# Mainboard-v18.net
KiCad netlist of a schematic drawn in EAGLE
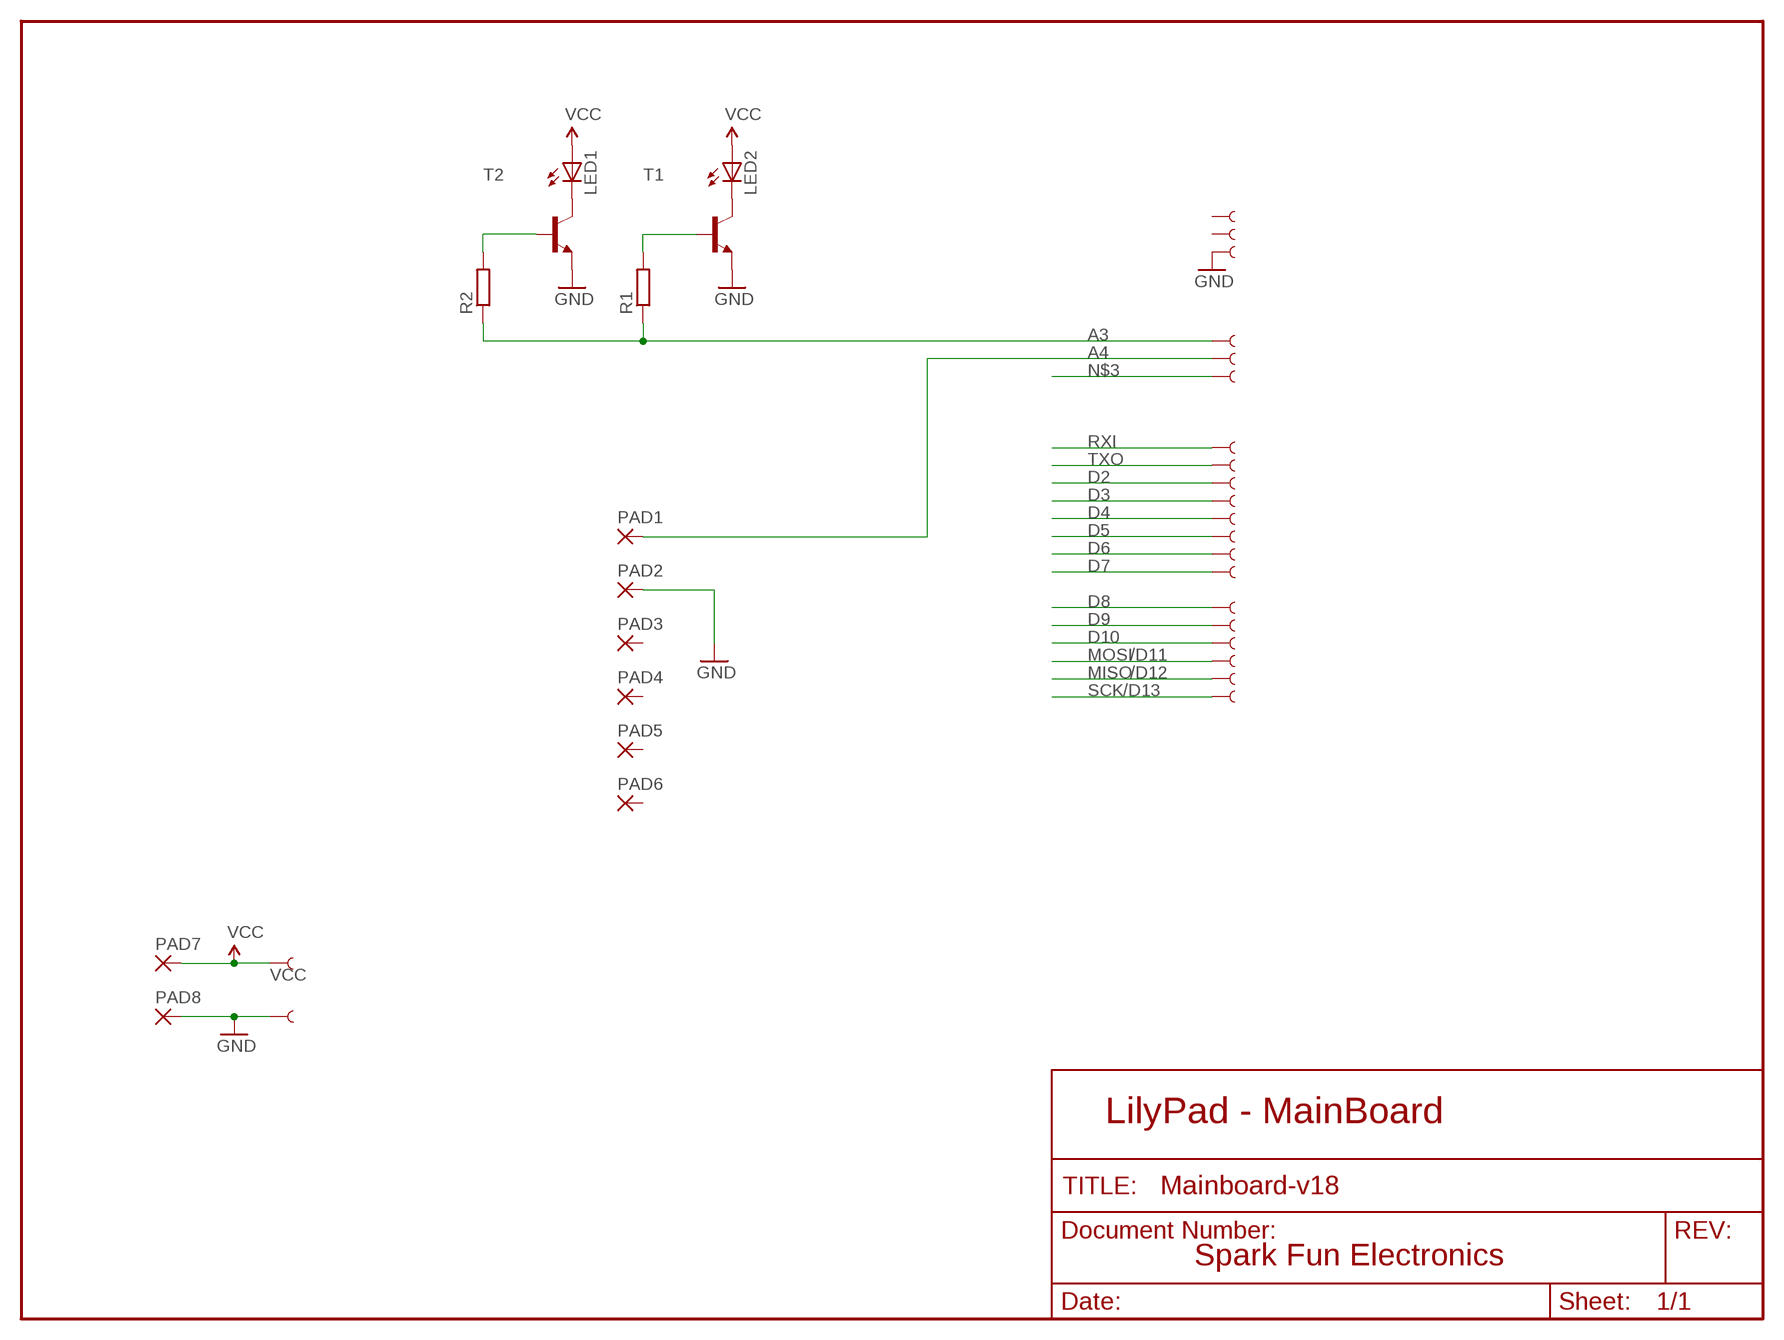
[diagram p0: schematic, sheet 1]

(export (version "E")
  (design (tool "Eeschema 10.0.6"))
  (components
    (comp (ref "GND")
      (value "SEWTAP1")
      (footprint "eagle-import:SEWTAP")
      (libsource (lib "eagle-import") (part "SEWTAP1"))
    )
    (comp (ref "LED1")
      (value "LED5MM")
      (footprint "eagle-import:LED5MM")
      (libsource (lib "eagle-import") (part "LED5MM"))
    )
    (comp (ref "LED2")
      (value "LED5MM")
      (footprint "eagle-import:LED5MM")
      (libsource (lib "eagle-import") (part "LED5MM"))
    )
    (comp (ref "PAD1")
      (value "1,6/0,8")
      (footprint "eagle-import:1,6_0,8")
      (libsource (lib "eagle-import") (part "1,6/0,8"))
    )
    (comp (ref "PAD2")
      (value "1,6/0,8")
      (footprint "eagle-import:1,6_0,8")
      (libsource (lib "eagle-import") (part "1,6/0,8"))
    )
    (comp (ref "PAD3")
      (value "1,6/0,8")
      (footprint "eagle-import:1,6_0,8")
      (libsource (lib "eagle-import") (part "1,6/0,8"))
    )
    (comp (ref "PAD4")
      (value "1,6/0,8")
      (footprint "eagle-import:1,6_0,8")
      (libsource (lib "eagle-import") (part "1,6/0,8"))
    )
    (comp (ref "PAD5")
      (value "1,6/0,8")
      (footprint "eagle-import:1,6_0,8")
      (libsource (lib "eagle-import") (part "1,6/0,8"))
    )
    (comp (ref "PAD6")
      (value "1,6/0,8")
      (footprint "eagle-import:1,6_0,8")
      (libsource (lib "eagle-import") (part "1,6/0,8"))
    )
    (comp (ref "PAD7")
      (value "1,6/0,8")
      (footprint "eagle-import:1,6_0,8")
      (libsource (lib "eagle-import") (part "1,6/0,8"))
    )
    (comp (ref "PAD8")
      (value "1,6/0,8")
      (footprint "eagle-import:1,6_0,8")
      (libsource (lib "eagle-import") (part "1,6/0,8"))
    )
    (comp (ref "R1")
      (value "R-EU_0204/5")
      (footprint "eagle-import:0204_5")
      (libsource (lib "eagle-import") (part "R-EU_0204/5"))
    )
    (comp (ref "R2")
      (value "R-EU_0204/5")
      (footprint "eagle-import:0204_5")
      (libsource (lib "eagle-import") (part "R-EU_0204/5"))
    )
    (comp (ref "T1")
      (value "2N3904")
      (footprint "eagle-import:TO92")
      (libsource (lib "eagle-import") (part "2N3904"))
    )
    (comp (ref "T2")
      (value "2N3904")
      (footprint "eagle-import:TO92")
      (libsource (lib "eagle-import") (part "2N3904"))
    )
    (comp (ref "U$4")
      (value "SEWTAP1")
      (footprint "eagle-import:SEWTAP")
      (libsource (lib "eagle-import") (part "SEWTAP1"))
    )
    (comp (ref "U$30")
      (value "SEWTAP1")
      (footprint "eagle-import:SEWTAP")
      (libsource (lib "eagle-import") (part "SEWTAP1"))
    )
    (comp (ref "U$31")
      (value "SEWTAP1")
      (footprint "eagle-import:SEWTAP")
      (libsource (lib "eagle-import") (part "SEWTAP1"))
    )
    (comp (ref "U$32")
      (value "SEWTAP1")
      (footprint "eagle-import:SEWTAP")
      (libsource (lib "eagle-import") (part "SEWTAP1"))
    )
    (comp (ref "U$33")
      (value "SEWTAP1")
      (footprint "eagle-import:SEWTAP")
      (libsource (lib "eagle-import") (part "SEWTAP1"))
    )
    (comp (ref "U$34")
      (value "SEWTAP1")
      (footprint "eagle-import:SEWTAP")
      (libsource (lib "eagle-import") (part "SEWTAP1"))
    )
    (comp (ref "U$35")
      (value "SEWTAP1")
      (footprint "eagle-import:SEWTAP")
      (libsource (lib "eagle-import") (part "SEWTAP1"))
    )
    (comp (ref "U$36")
      (value "SEWTAP1")
      (footprint "eagle-import:SEWTAP")
      (libsource (lib "eagle-import") (part "SEWTAP1"))
    )
    (comp (ref "U$37")
      (value "SEWTAP1")
      (footprint "eagle-import:SEWTAP")
      (libsource (lib "eagle-import") (part "SEWTAP1"))
    )
    (comp (ref "U$38")
      (value "SEWTAP1")
      (footprint "eagle-import:SEWTAP")
      (libsource (lib "eagle-import") (part "SEWTAP1"))
    )
    (comp (ref "U$39")
      (value "SEWTAP1")
      (footprint "eagle-import:SEWTAP")
      (libsource (lib "eagle-import") (part "SEWTAP1"))
    )
    (comp (ref "U$40")
      (value "SEWTAP1")
      (footprint "eagle-import:SEWTAP")
      (libsource (lib "eagle-import") (part "SEWTAP1"))
    )
    (comp (ref "U$41")
      (value "SEWTAP1")
      (footprint "eagle-import:SEWTAP")
      (libsource (lib "eagle-import") (part "SEWTAP1"))
    )
    (comp (ref "U$42")
      (value "SEWTAP1")
      (footprint "eagle-import:SEWTAP")
      (libsource (lib "eagle-import") (part "SEWTAP1"))
    )
    (comp (ref "U$43")
      (value "SEWTAP1")
      (footprint "eagle-import:SEWTAP")
      (libsource (lib "eagle-import") (part "SEWTAP1"))
    )
    (comp (ref "U$44")
      (value "SEWTAP1")
      (footprint "eagle-import:SEWTAP")
      (libsource (lib "eagle-import") (part "SEWTAP1"))
    )
    (comp (ref "U$45")
      (value "SEWTAP1")
      (footprint "eagle-import:SEWTAP")
      (libsource (lib "eagle-import") (part "SEWTAP1"))
    )
    (comp (ref "U$46")
      (value "SEWTAP1")
      (footprint "eagle-import:SEWTAP")
      (libsource (lib "eagle-import") (part "SEWTAP1"))
    )
    (comp (ref "U$47")
      (value "SEWTAP1")
      (footprint "eagle-import:SEWTAP")
      (libsource (lib "eagle-import") (part "SEWTAP1"))
    )
    (comp (ref "U$48")
      (value "SEWTAP1")
      (footprint "eagle-import:SEWTAP")
      (libsource (lib "eagle-import") (part "SEWTAP1"))
    )
    (comp (ref "U$51")
      (value "SEWTAP1")
      (footprint "eagle-import:SEWTAP")
      (libsource (lib "eagle-import") (part "SEWTAP1"))
    )
  )
  (nets
    (net (code "1") (name "/A3") (class "Default")
      (node (ref "R1") (pin "1") (pinfunction "1_1") (pintype "passive"))
      (node (ref "R2") (pin "1") (pinfunction "1_1") (pintype "passive"))
      (node (ref "U$32") (pin "1") (pinfunction "1_1") (pintype "bidirectional"))
    )
    (net (code "2") (name "/A4") (class "Default")
      (node (ref "PAD1") (pin "1") (pinfunction "P_1") (pintype "passive"))
      (node (ref "U$33") (pin "1") (pinfunction "1_1") (pintype "bidirectional"))
    )
    (net (code "3") (name "/D2") (class "Default")
      (node (ref "U$45") (pin "1") (pinfunction "1_1") (pintype "bidirectional"))
    )
    (net (code "4") (name "/D3") (class "Default")
      (node (ref "U$44") (pin "1") (pinfunction "1_1") (pintype "bidirectional"))
    )
    (net (code "5") (name "/D4") (class "Default")
      (node (ref "U$43") (pin "1") (pinfunction "1_1") (pintype "bidirectional"))
    )
    (net (code "6") (name "/D5") (class "Default")
      (node (ref "U$42") (pin "1") (pinfunction "1_1") (pintype "bidirectional"))
    )
    (net (code "7") (name "/D6") (class "Default")
      (node (ref "U$41") (pin "1") (pinfunction "1_1") (pintype "bidirectional"))
    )
    (net (code "8") (name "/D7") (class "Default")
      (node (ref "U$48") (pin "1") (pinfunction "1_1") (pintype "bidirectional"))
    )
    (net (code "9") (name "/D8") (class "Default")
      (node (ref "U$35") (pin "1") (pinfunction "1_1") (pintype "bidirectional"))
    )
    (net (code "10") (name "/D9") (class "Default")
      (node (ref "U$36") (pin "1") (pinfunction "1_1") (pintype "bidirectional"))
    )
    (net (code "11") (name "/D10") (class "Default")
      (node (ref "U$37") (pin "1") (pinfunction "1_1") (pintype "bidirectional"))
    )
    (net (code "12") (name "/MISO") (class "Default")
      (node (ref "U$39") (pin "1") (pinfunction "1_1") (pintype "bidirectional"))
    )
    (net (code "13") (name "/MOSI") (class "Default")
      (node (ref "U$38") (pin "1") (pinfunction "1_1") (pintype "bidirectional"))
    )
    (net (code "14") (name "/N$3") (class "Default")
      (node (ref "U$34") (pin "1") (pinfunction "1_1") (pintype "bidirectional"))
    )
    (net (code "15") (name "/RXI") (class "Default")
      (node (ref "U$47") (pin "1") (pinfunction "1_1") (pintype "bidirectional"))
    )
    (net (code "16") (name "/SCK") (class "Default")
      (node (ref "U$40") (pin "1") (pinfunction "1_1") (pintype "bidirectional"))
    )
    (net (code "17") (name "/TXO") (class "Default")
      (node (ref "U$46") (pin "1") (pinfunction "1_1") (pintype "bidirectional"))
    )
    (net (code "18") (name "GND") (class "Default")
      (node (ref "PAD2") (pin "1") (pinfunction "P_1") (pintype "passive"))
      (node (ref "PAD8") (pin "1") (pinfunction "P_1") (pintype "passive"))
      (node (ref "T1") (pin "3") (pinfunction "E_3") (pintype "passive"))
      (node (ref "T2") (pin "3") (pinfunction "E_3") (pintype "passive"))
      (node (ref "U$30") (pin "1") (pinfunction "1_1") (pintype "bidirectional"))
      (node (ref "U$31") (pin "1") (pinfunction "1_1") (pintype "bidirectional"))
    )
    (net (code "19") (name "Net-(LED1-C)") (class "Default")
      (node (ref "LED1") (pin "K") (pinfunction "C_K") (pintype "passive"))
      (node (ref "T2") (pin "1") (pinfunction "C_1") (pintype "passive"))
    )
    (net (code "20") (name "Net-(LED2-C)") (class "Default")
      (node (ref "LED2") (pin "K") (pinfunction "C_K") (pintype "passive"))
      (node (ref "T1") (pin "1") (pinfunction "C_1") (pintype "passive"))
    )
    (net (code "21") (name "Net-(T1-B)") (class "Default")
      (node (ref "R1") (pin "2") (pinfunction "2_2") (pintype "passive"))
      (node (ref "T1") (pin "2") (pinfunction "B_2") (pintype "passive"))
    )
    (net (code "22") (name "Net-(T2-B)") (class "Default")
      (node (ref "R2") (pin "2") (pinfunction "2_2") (pintype "passive"))
      (node (ref "T2") (pin "2") (pinfunction "B_2") (pintype "passive"))
    )
    (net (code "23") (name "VCC") (class "Default")
      (node (ref "LED1") (pin "A") (pinfunction "A_A") (pintype "passive"))
      (node (ref "LED2") (pin "A") (pinfunction "A_A") (pintype "passive"))
      (node (ref "PAD7") (pin "1") (pinfunction "P_1") (pintype "passive"))
      (node (ref "U$4") (pin "1") (pinfunction "1_1") (pintype "bidirectional"))
    )
    (net (code "24") (name "unconnected-(GND-Pad1)") (class "Default")
      (node (ref "GND") (pin "1") (pinfunction "1_1") (pintype "bidirectional"))
    )
    (net (code "25") (name "unconnected-(PAD3-P-Pad1)") (class "Default")
      (node (ref "PAD3") (pin "1") (pinfunction "P_1") (pintype "passive"))
    )
    (net (code "26") (name "unconnected-(PAD4-P-Pad1)") (class "Default")
      (node (ref "PAD4") (pin "1") (pinfunction "P_1") (pintype "passive"))
    )
    (net (code "27") (name "unconnected-(PAD5-P-Pad1)") (class "Default")
      (node (ref "PAD5") (pin "1") (pinfunction "P_1") (pintype "passive"))
    )
    (net (code "28") (name "unconnected-(PAD6-P-Pad1)") (class "Default")
      (node (ref "PAD6") (pin "1") (pinfunction "P_1") (pintype "passive"))
    )
    (net (code "29") (name "unconnected-(U$51-Pad1)") (class "Default")
      (node (ref "U$51") (pin "1") (pinfunction "1_1") (pintype "bidirectional"))
    )
  )
)
